# arduinoboard.net
KiCad netlist of a schematic drawn in EAGLE
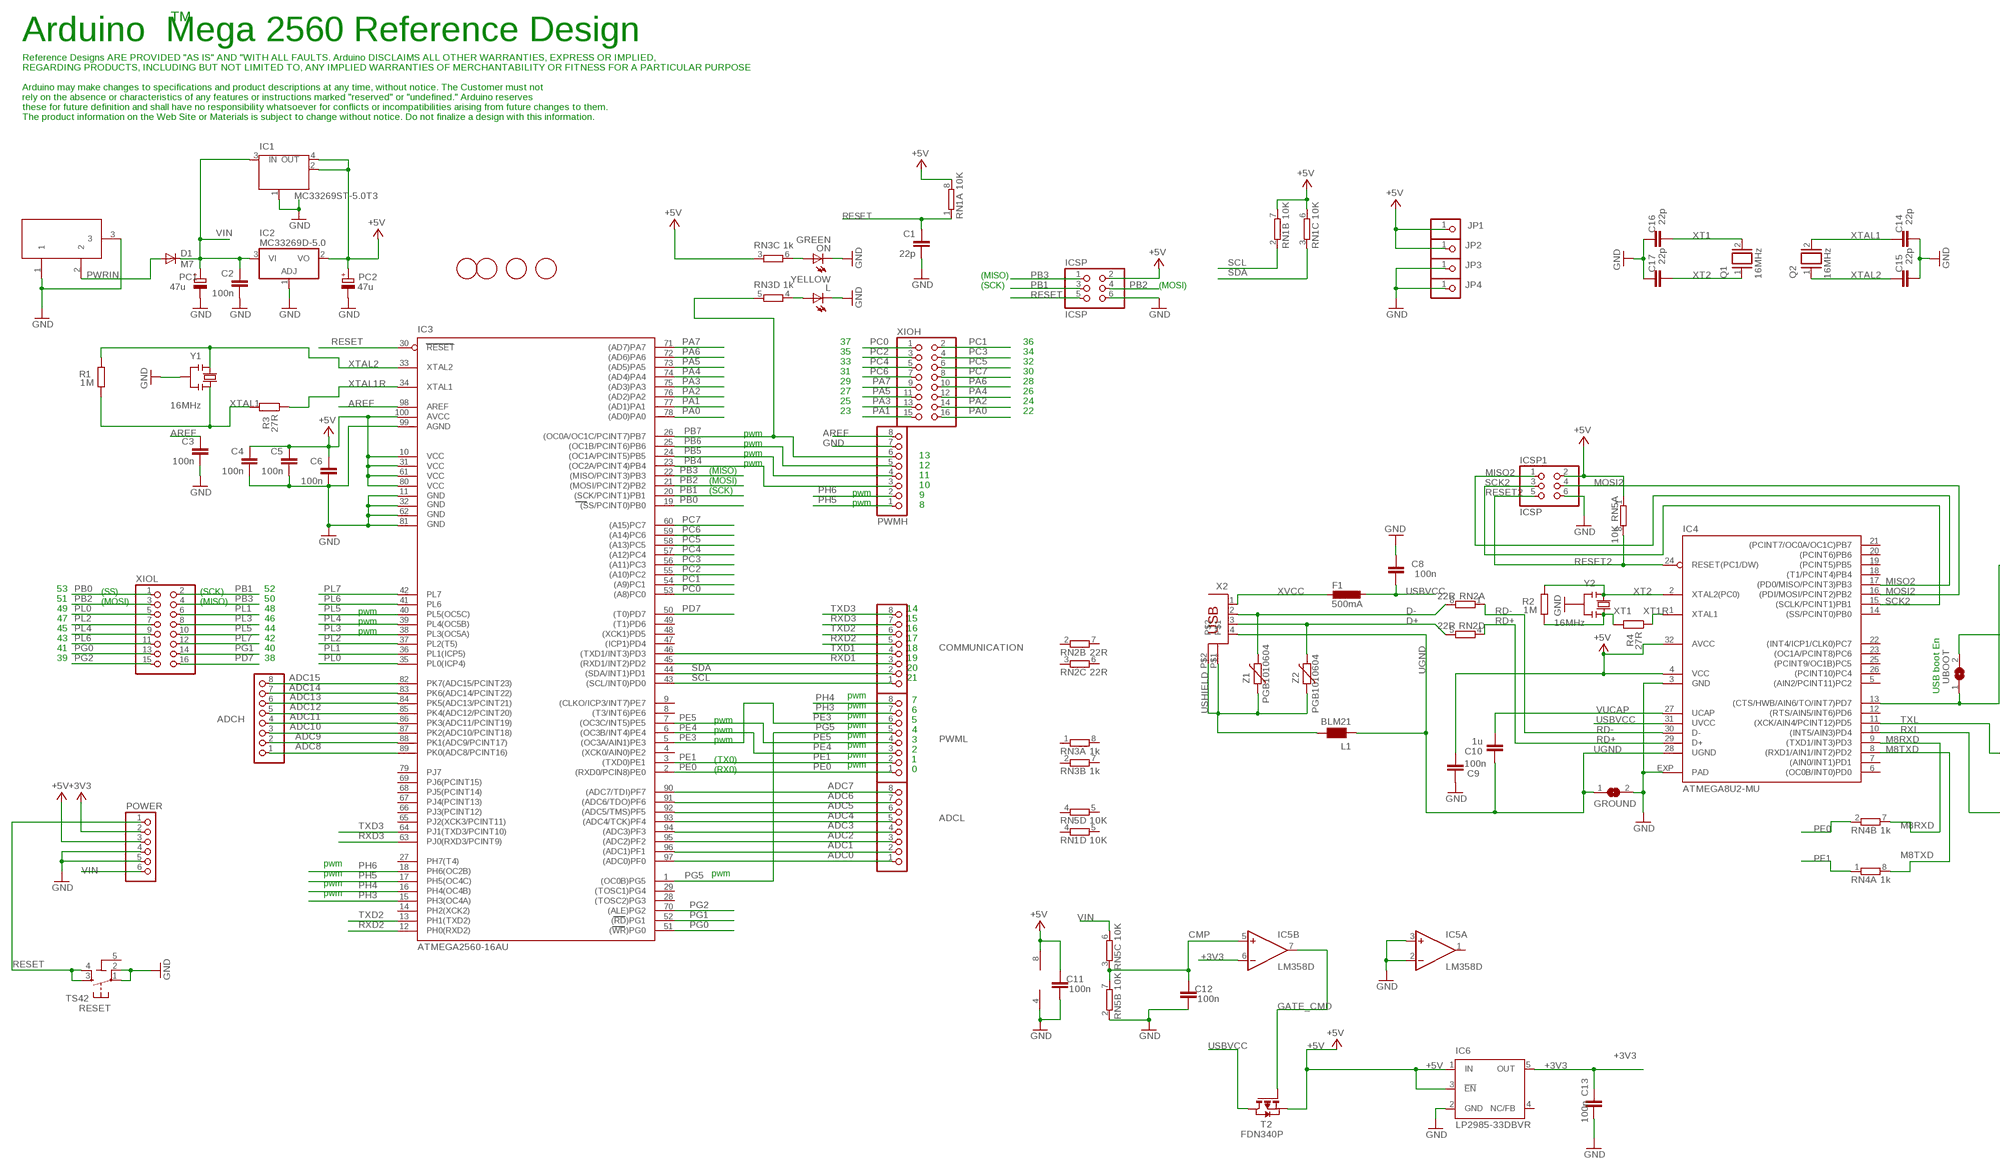
[diagram p0: schematic, sheet 1, part 1 of 2]
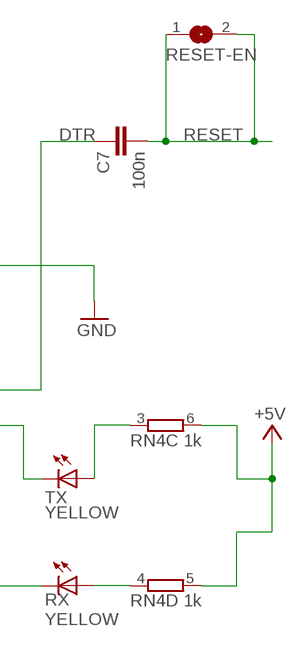
[diagram p1: schematic, sheet 1, part 2 of 2]

(export (version "E")
  (design (tool "Eeschema 10.0.6"))
  (components
    (comp (ref "ADCH")
      (value "PINHD-1X8")
      (footprint "eagle-import:1X08")
      (libsource (lib "eagle-import") (part "PINHD-1X8"))
    )
    (comp (ref "ADCL")
      (value "PINHD-1X8")
      (footprint "eagle-import:1X08")
      (libsource (lib "eagle-import") (part "PINHD-1X8"))
    )
    (comp (ref "C1")
      (value "22p")
      (footprint "eagle-import:C0603-ROUND")
      (libsource (lib "eagle-import") (part "C-EU0603-RND"))
    )
    (comp (ref "C2")
      (value "100n")
      (footprint "eagle-import:C0603-ROUND")
      (libsource (lib "eagle-import") (part "C-EU0603-RND"))
    )
    (comp (ref "C3")
      (value "100n")
      (footprint "eagle-import:C0603-ROUND")
      (libsource (lib "eagle-import") (part "C-EU0603-RND"))
    )
    (comp (ref "C4")
      (value "100n")
      (footprint "eagle-import:C0603-ROUND")
      (libsource (lib "eagle-import") (part "C-EU0603-RND"))
    )
    (comp (ref "C5")
      (value "100n")
      (footprint "eagle-import:C0603-ROUND")
      (libsource (lib "eagle-import") (part "C-EU0603-RND"))
    )
    (comp (ref "C6")
      (value "100n")
      (footprint "eagle-import:C0603-ROUND")
      (libsource (lib "eagle-import") (part "C-EU0603-RND"))
    )
    (comp (ref "C7")
      (value "100n")
      (footprint "eagle-import:C0603-ROUND")
      (libsource (lib "eagle-import") (part "C-EU0603-RND"))
    )
    (comp (ref "C8")
      (value "100n")
      (footprint "eagle-import:C0603")
      (libsource (lib "eagle-import") (part "rcl_C-EUC0603"))
    )
    (comp (ref "C9")
      (value "100n")
      (footprint "eagle-import:C0603-ROUND")
      (libsource (lib "eagle-import") (part "C-EU0603-RND"))
    )
    (comp (ref "C10")
      (value "1u")
      (footprint "eagle-import:C0603-ROUND")
      (libsource (lib "eagle-import") (part "C-EU0603-RND"))
    )
    (comp (ref "C11")
      (value "100n")
      (footprint "eagle-import:C0603")
      (libsource (lib "eagle-import") (part "rcl_C-EUC0603"))
    )
    (comp (ref "C12")
      (value "100n")
      (footprint "eagle-import:C0603-ROUND")
      (libsource (lib "eagle-import") (part "C-EU0603-RND"))
    )
    (comp (ref "C13")
      (value "100n")
      (footprint "eagle-import:C0603-ROUND")
      (libsource (lib "eagle-import") (part "C-EU0603-RND"))
    )
    (comp (ref "C14")
      (value "22p")
      (footprint "eagle-import:C0603-ROUND")
      (libsource (lib "eagle-import") (part "C-EU0603-RND"))
    )
    (comp (ref "C15")
      (value "22p")
      (footprint "eagle-import:C0603-ROUND")
      (libsource (lib "eagle-import") (part "C-EU0603-RND"))
    )
    (comp (ref "C16")
      (value "22p")
      (footprint "eagle-import:C0603-ROUND")
      (libsource (lib "eagle-import") (part "C-EU0603-RND"))
    )
    (comp (ref "C17")
      (value "22p")
      (footprint "eagle-import:C0603-ROUND")
      (libsource (lib "eagle-import") (part "C-EU0603-RND"))
    )
    (comp (ref "COMMUNICATION")
      (value "PINHD-1X8")
      (footprint "eagle-import:1X08")
      (libsource (lib "eagle-import") (part "PINHD-1X8"))
    )
    (comp (ref "D1")
      (value "M7")
      (footprint "eagle-import:SMB")
      (libsource (lib "eagle-import") (part "DIODE-SMB"))
    )
    (comp (ref "F1")
      (value "500mA")
      (footprint "eagle-import:L1812")
      (libsource (lib "eagle-import") (part "L-EUL1812"))
    )
    (comp (ref "GROUND")
      (value "SJ")
      (footprint "eagle-import:SJ")
      (libsource (lib "eagle-import") (part "SJ"))
    )
    (comp (ref "IC1")
      (value "MC33269ST-5.0T3")
      (footprint "eagle-import:SOT223")
      (libsource (lib "eagle-import") (part "MC33269ST-3.3T3"))
    )
    (comp (ref "IC2")
      (value "MC33269D-5.0")
      (footprint "eagle-import:DPACK")
      (libsource (lib "eagle-import") (part "MC33269?D-5.0"))
    )
    (comp (ref "IC3")
      (value "ATMEGA2560-16AU")
      (footprint "eagle-import:TQFP100")
      (libsource (lib "eagle-import") (part "ATMEGAAU1280-16"))
    )
    (comp (ref "IC4")
      (value "ATMEGA8U2-MU")
      (footprint "eagle-import:QFN32")
      (libsource (lib "eagle-import") (part "ATMEGA8U2-MU"))
    )
    (comp (ref "IC5")
      (value "LM358D")
      (footprint "eagle-import:SO08")
      (libsource (lib "eagle-import") (part "LM358D"))
    )
    (comp (ref "IC6")
      (value "LP2985-33DBVR")
      (footprint "eagle-import:SOT23-DBV")
      (libsource (lib "eagle-import") (part "TPS77033"))
    )
    (comp (ref "ICSP")
      (value "ICSP")
      (footprint "eagle-import:2X03")
      (libsource (lib "eagle-import") (part "PINHD-2X3"))
    )
    (comp (ref "ICSP1")
      (value "ICSP")
      (footprint "eagle-import:2X03")
      (libsource (lib "eagle-import") (part "PINHD-2X3"))
    )
    (comp (ref "JP1")
      (value "PINHD-1X1")
      (footprint "eagle-import:1X01")
      (libsource (lib "eagle-import") (part "PINHD-1X1"))
    )
    (comp (ref "JP2")
      (value "PINHD-1X1")
      (footprint "eagle-import:1X01")
      (libsource (lib "eagle-import") (part "PINHD-1X1"))
    )
    (comp (ref "JP3")
      (value "PINHD-1X1")
      (footprint "eagle-import:1X01")
      (libsource (lib "eagle-import") (part "PINHD-1X1"))
    )
    (comp (ref "JP4")
      (value "PINHD-1X1")
      (footprint "eagle-import:1X01")
      (libsource (lib "eagle-import") (part "PINHD-1X1"))
    )
    (comp (ref "L")
      (value "YELLOW")
      (footprint "eagle-import:CHIP-LED0805")
      (libsource (lib "eagle-import") (part "LEDCHIP-LED0805"))
    )
    (comp (ref "L1")
      (value "BLM21")
      (footprint "eagle-import:0805")
      (libsource (lib "eagle-import") (part "WE-CBF_0805"))
    )
    (comp (ref "ON")
      (value "GREEN")
      (footprint "eagle-import:CHIP-LED0805")
      (libsource (lib "eagle-import") (part "LEDCHIP-LED0805"))
    )
    (comp (ref "PC1")
      (value "47u")
      (footprint "eagle-import:PANASONIC_D")
      (libsource (lib "eagle-import") (part "CPOL-EUD"))
    )
    (comp (ref "PC2")
      (value "47u")
      (footprint "eagle-import:PANASONIC_D")
      (libsource (lib "eagle-import") (part "CPOL-EUD"))
    )
    (comp (ref "POWER")
      (value "PINHD-1X6")
      (footprint "eagle-import:1X06")
      (libsource (lib "eagle-import") (part "PINHD-1X6"))
    )
    (comp (ref "PWMH")
      (value "PINHD-1X8")
      (footprint "eagle-import:1X08")
      (libsource (lib "eagle-import") (part "PINHD-1X8"))
    )
    (comp (ref "PWML")
      (value "PINHD-1X8")
      (footprint "eagle-import:1X08")
      (libsource (lib "eagle-import") (part "PINHD-1X8"))
    )
    (comp (ref "Q1")
      (value "16MHz")
      (footprint "eagle-import:QS")
      (libsource (lib "eagle-import") (part "XTAL/S"))
    )
    (comp (ref "Q2")
      (value "16MHz")
      (footprint "eagle-import:QS")
      (libsource (lib "eagle-import") (part "XTAL/S"))
    )
    (comp (ref "R1")
      (value "1M")
      (footprint "eagle-import:R0603-ROUND")
      (libsource (lib "eagle-import") (part "R-EU_R0603"))
    )
    (comp (ref "R2")
      (value "1M")
      (footprint "eagle-import:R0603-ROUND")
      (libsource (lib "eagle-import") (part "R-EU_R0603"))
    )
    (comp (ref "R3")
      (value "27R")
      (footprint "eagle-import:R0603-ROUND")
      (libsource (lib "eagle-import") (part "R-EU_R0603"))
    )
    (comp (ref "R4")
      (value "27R")
      (footprint "eagle-import:R0603-ROUND")
      (libsource (lib "eagle-import") (part "R-EU_R0603"))
    )
    (comp (ref "RESET")
      (value "TS42")
      (footprint "eagle-import:TS42")
      (libsource (lib "eagle-import") (part "TS42"))
    )
    (comp (ref "RESET-EN")
      (value "SJ")
      (footprint "eagle-import:SJ")
      (libsource (lib "eagle-import") (part "SJ"))
    )
    (comp (ref "RN1")
      (value "10K")
      (footprint "eagle-import:CAT16")
      (libsource (lib "eagle-import") (part "4R-NCAT16"))
    )
    (comp (ref "RN2")
      (value "22R")
      (footprint "eagle-import:CAY16")
      (libsource (lib "eagle-import") (part "4R-NCAY16"))
    )
    (comp (ref "RN3")
      (value "1k")
      (footprint "eagle-import:CAY16")
      (libsource (lib "eagle-import") (part "4R-NCAY16"))
    )
    (comp (ref "RN4")
      (value "1k")
      (footprint "eagle-import:CAY16")
      (libsource (lib "eagle-import") (part "4R-NCAY16"))
    )
    (comp (ref "RN5")
      (value "10K")
      (footprint "eagle-import:CAT16")
      (libsource (lib "eagle-import") (part "4R-NCAT16"))
    )
    (comp (ref "RX")
      (value "YELLOW")
      (footprint "eagle-import:CHIP-LED0805")
      (libsource (lib "eagle-import") (part "LEDCHIP-LED0805"))
    )
    (comp (ref "T2")
      (value "FDN340P")
      (footprint "eagle-import:SOT-23")
      (libsource (lib "eagle-import") (part "PMOSSOT23"))
    )
    (comp (ref "TX")
      (value "YELLOW")
      (footprint "eagle-import:CHIP-LED0805")
      (libsource (lib "eagle-import") (part "LEDCHIP-LED0805"))
    )
    (comp (ref "U$2")
      (value "FIDUCIALMOUNT")
      (footprint "eagle-import:FIDUCIA-MOUNT")
      (libsource (lib "eagle-import") (part "FIDUCIALMOUNT"))
    )
    (comp (ref "U$3")
      (value "FIDUCIALMOUNT")
      (footprint "eagle-import:FIDUCIA-MOUNT")
      (libsource (lib "eagle-import") (part "FIDUCIALMOUNT"))
    )
    (comp (ref "U$4")
      (value "FIDUCIALMOUNT")
      (footprint "eagle-import:FIDUCIA-MOUNT")
      (libsource (lib "eagle-import") (part "FIDUCIALMOUNT"))
    )
    (comp (ref "U$5")
      (value "FIDUCIALMOUNT")
      (footprint "eagle-import:FIDUCIA-MOUNT")
      (libsource (lib "eagle-import") (part "FIDUCIALMOUNT"))
    )
    (comp (ref "UBOOT")
      (value "SJ")
      (footprint "eagle-import:SJ")
      (libsource (lib "eagle-import") (part "SJ"))
    )
    (comp (ref "X1")
      (value "DC21MMX")
      (footprint "eagle-import:DC-21MM")
      (libsource (lib "eagle-import") (part "DC21MMX"))
    )
    (comp (ref "X2")
      (value "PN61729")
      (footprint "eagle-import:PN61729")
      (libsource (lib "eagle-import") (part "PN61729"))
    )
    (comp (ref "XIOH")
      (value "PINHD-2X8")
      (footprint "eagle-import:2X08")
      (libsource (lib "eagle-import") (part "PINHD-2X8"))
    )
    (comp (ref "XIOL")
      (value "PINHD-2X8")
      (footprint "eagle-import:2X08")
      (libsource (lib "eagle-import") (part "PINHD-2X8"))
    )
    (comp (ref "Y1")
      (value "16MHz")
      (footprint "eagle-import:RESONATOR")
      (libsource (lib "eagle-import") (part "RESONATORMU"))
    )
    (comp (ref "Y2")
      (value "16MHz")
      (footprint "eagle-import:RESONATOR")
      (libsource (lib "eagle-import") (part "RESONATORMU"))
    )
    (comp (ref "Z1")
      (value "PGB1010604")
      (footprint "eagle-import:CT_CN0603")
      (libsource (lib "eagle-import") (part "VARISTORCN0603"))
    )
    (comp (ref "Z2")
      (value "PGB1010604")
      (footprint "eagle-import:CT_CN0603")
      (libsource (lib "eagle-import") (part "VARISTORCN0603"))
    )
  )
  (nets
    (net (code "1") (name "+3V3") (class "Default")
      (node (ref "C13") (pin "2") (pinfunction "2_2") (pintype "passive"))
      (node (ref "IC5") (pin "6") (pinfunction "-IN_6") (pintype "input"))
      (node (ref "IC6") (pin "5") (pinfunction "OUT_5") (pintype "passive"))
      (node (ref "POWER") (pin "2") (pinfunction "2_2") (pintype "passive"))
    )
    (net (code "2") (name "+5V") (class "Default")
      (node (ref "C11") (pin "2") (pinfunction "2_2") (pintype "passive"))
      (node (ref "C4") (pin "1") (pinfunction "1_1") (pintype "passive"))
      (node (ref "C5") (pin "1") (pinfunction "1_1") (pintype "passive"))
      (node (ref "C6") (pin "1") (pinfunction "1_1") (pintype "passive"))
      (node (ref "C9") (pin "1") (pinfunction "1_1") (pintype "passive"))
      (node (ref "IC1") (pin "2") (pinfunction "OUT_2") (pintype "passive"))
      (node (ref "IC1") (pin "4") (pinfunction "OUT_4") (pintype "passive"))
      (node (ref "IC2") (pin "2") (pinfunction "VO_2") (pintype "passive"))
      (node (ref "IC3") (pin "10") (pinfunction "VCC_10") (pintype "power_in"))
      (node (ref "IC3") (pin "100") (pinfunction "AVCC_100") (pintype "power_in"))
      (node (ref "IC3") (pin "31") (pinfunction "VCC1_31") (pintype "power_in"))
      (node (ref "IC3") (pin "61") (pinfunction "VCC2_61") (pintype "power_in"))
      (node (ref "IC3") (pin "80") (pinfunction "VCC3_80") (pintype "power_in"))
      (node (ref "IC4") (pin "32") (pinfunction "AVCC_32") (pintype "power_in"))
      (node (ref "IC4") (pin "4") (pinfunction "VCC_4") (pintype "power_in"))
      (node (ref "IC5") (pin "8") (pinfunction "V+_8") (pintype "power_in"))
      (node (ref "IC6") (pin "1") (pinfunction "IN_1") (pintype "input"))
      (node (ref "IC6") (pin "3") (pinfunction "~{EN}_3") (pintype "input"))
      (node (ref "ICSP") (pin "2") (pinfunction "2_2") (pintype "passive"))
      (node (ref "ICSP1") (pin "2") (pinfunction "2_2") (pintype "passive"))
      (node (ref "JP1") (pin "1") (pinfunction "1_1") (pintype "passive"))
      (node (ref "JP2") (pin "1") (pinfunction "1_1") (pintype "passive"))
      (node (ref "PC2") (pin "+") (pinfunction "+_+") (pintype "passive"))
      (node (ref "POWER") (pin "3") (pinfunction "3_3") (pintype "passive"))
      (node (ref "RN1") (pin "6") (pinfunction "2_6") (pintype "passive"))
      (node (ref "RN1") (pin "7") (pinfunction "2_7") (pintype "passive"))
      (node (ref "RN1") (pin "8") (pinfunction "2_8") (pintype "passive"))
      (node (ref "RN3") (pin "3") (pinfunction "1_3") (pintype "passive"))
      (node (ref "RN4") (pin "5") (pinfunction "2_5") (pintype "passive"))
      (node (ref "RN4") (pin "6") (pinfunction "2_6") (pintype "passive"))
      (node (ref "RN5") (pin "1") (pinfunction "1_1") (pintype "passive"))
      (node (ref "T2") (pin "2") (pinfunction "S_2") (pintype "passive"))
    )
    (net (code "3") (name "/5-GND") (class "Default")
      (node (ref "RESET") (pin "5") (pinfunction "5-GND_5") (pintype "power_in"))
    )
    (net (code "4") (name "/ADC0") (class "Default")
      (node (ref "ADCL") (pin "1") (pinfunction "1_1") (pintype "passive"))
      (node (ref "IC3") (pin "97") (pinfunction "(ADC0)PF0_97") (pintype "bidirectional"))
    )
    (net (code "5") (name "/ADC1") (class "Default")
      (node (ref "ADCL") (pin "2") (pinfunction "2_2") (pintype "passive"))
      (node (ref "IC3") (pin "96") (pinfunction "(ADC1)PF1_96") (pintype "bidirectional"))
    )
    (net (code "6") (name "/ADC2") (class "Default")
      (node (ref "ADCL") (pin "3") (pinfunction "3_3") (pintype "passive"))
      (node (ref "IC3") (pin "95") (pinfunction "(ADC2)PF2_95") (pintype "bidirectional"))
    )
    (net (code "7") (name "/ADC3") (class "Default")
      (node (ref "ADCL") (pin "4") (pinfunction "4_4") (pintype "passive"))
      (node (ref "IC3") (pin "94") (pinfunction "(ADC3)PF3_94") (pintype "bidirectional"))
    )
    (net (code "8") (name "/ADC4") (class "Default")
      (node (ref "ADCL") (pin "5") (pinfunction "5_5") (pintype "passive"))
      (node (ref "IC3") (pin "93") (pinfunction "(ADC4/TCK)PF4_93") (pintype "bidirectional"))
    )
    (net (code "9") (name "/ADC5") (class "Default")
      (node (ref "ADCL") (pin "6") (pinfunction "6_6") (pintype "passive"))
      (node (ref "IC3") (pin "92") (pinfunction "(ADC5/TMS)PF5_92") (pintype "bidirectional"))
    )
    (net (code "10") (name "/ADC6") (class "Default")
      (node (ref "ADCL") (pin "7") (pinfunction "7_7") (pintype "passive"))
      (node (ref "IC3") (pin "91") (pinfunction "(ADC6/TDO)PF6_91") (pintype "bidirectional"))
    )
    (net (code "11") (name "/ADC7") (class "Default")
      (node (ref "ADCL") (pin "8") (pinfunction "8_8") (pintype "passive"))
      (node (ref "IC3") (pin "90") (pinfunction "(ADC7/TDI)PF7_90") (pintype "bidirectional"))
    )
    (net (code "12") (name "/ADC8") (class "Default")
      (node (ref "ADCH") (pin "1") (pinfunction "1_1") (pintype "passive"))
      (node (ref "IC3") (pin "89") (pinfunction "PK0(ADC8/PCINT16)_89") (pintype "bidirectional"))
    )
    (net (code "13") (name "/ADC9") (class "Default")
      (node (ref "ADCH") (pin "2") (pinfunction "2_2") (pintype "passive"))
      (node (ref "IC3") (pin "88") (pinfunction "PK1(ADC9/PCINT17)_88") (pintype "bidirectional"))
    )
    (net (code "14") (name "/ADC10") (class "Default")
      (node (ref "ADCH") (pin "3") (pinfunction "3_3") (pintype "passive"))
      (node (ref "IC3") (pin "87") (pinfunction "PK2(ADC10/PCINT18)_87") (pintype "bidirectional"))
    )
    (net (code "15") (name "/ADC11") (class "Default")
      (node (ref "ADCH") (pin "4") (pinfunction "4_4") (pintype "passive"))
      (node (ref "IC3") (pin "86") (pinfunction "PK3(ADC11/PCINT19)_86") (pintype "bidirectional"))
    )
    (net (code "16") (name "/ADC12") (class "Default")
      (node (ref "ADCH") (pin "5") (pinfunction "5_5") (pintype "passive"))
      (node (ref "IC3") (pin "85") (pinfunction "PK4(ADC12/PCINT20)_85") (pintype "bidirectional"))
    )
    (net (code "17") (name "/ADC13") (class "Default")
      (node (ref "ADCH") (pin "6") (pinfunction "6_6") (pintype "passive"))
      (node (ref "IC3") (pin "84") (pinfunction "PK5(ADC13/PCINT21)_84") (pintype "bidirectional"))
    )
    (net (code "18") (name "/ADC14") (class "Default")
      (node (ref "ADCH") (pin "7") (pinfunction "7_7") (pintype "passive"))
      (node (ref "IC3") (pin "83") (pinfunction "PK6(ADC14/PCINT22)_83") (pintype "bidirectional"))
    )
    (net (code "19") (name "/ADC15") (class "Default")
      (node (ref "ADCH") (pin "8") (pinfunction "8_8") (pintype "passive"))
      (node (ref "IC3") (pin "82") (pinfunction "PK7(ADC15/PCINT23)_82") (pintype "bidirectional"))
    )
    (net (code "20") (name "/AREF") (class "Default")
      (node (ref "C3") (pin "1") (pinfunction "1_1") (pintype "passive"))
      (node (ref "IC3") (pin "98") (pinfunction "AREF_98") (pintype "bidirectional"))
      (node (ref "PWMH") (pin "8") (pinfunction "8_8") (pintype "passive"))
    )
    (net (code "21") (name "/CMP") (class "Default")
      (node (ref "C12") (pin "2") (pinfunction "2_2") (pintype "passive"))
      (node (ref "IC5") (pin "5") (pinfunction "+IN_5") (pintype "input"))
      (node (ref "RN5") (pin "3") (pinfunction "1_3") (pintype "passive"))
      (node (ref "RN5") (pin "7") (pinfunction "2_7") (pintype "passive"))
    )
    (net (code "22") (name "/D+") (class "Default")
      (node (ref "RN2") (pin "5") (pinfunction "2_5") (pintype "passive"))
      (node (ref "X2") (pin "3") (pinfunction "3_3") (pintype "bidirectional"))
      (node (ref "Z2") (pin "2") (pinfunction "2_2") (pintype "passive"))
    )
    (net (code "23") (name "/D-") (class "Default")
      (node (ref "RN2") (pin "8") (pinfunction "2_8") (pintype "passive"))
      (node (ref "X2") (pin "2") (pinfunction "2_2") (pintype "bidirectional"))
      (node (ref "Z1") (pin "2") (pinfunction "2_2") (pintype "passive"))
    )
    (net (code "24") (name "/DTR") (class "Default")
      (node (ref "C7") (pin "1") (pinfunction "1_1") (pintype "passive"))
      (node (ref "IC4") (pin "13") (pinfunction "(CTS/HWB/AIN6/TO/INT7)PD7_13") (pintype "bidirectional"))
      (node (ref "UBOOT") (pin "1") (pinfunction "1_1") (pintype "passive"))
    )
    (net (code "25") (name "/GATE_CMD") (class "Default")
      (node (ref "IC5") (pin "7") (pinfunction "OUT_7") (pintype "output"))
      (node (ref "T2") (pin "3") (pinfunction "G_3") (pintype "passive"))
    )
    (net (code "26") (name "/M8RXD") (class "Default")
      (node (ref "IC4") (pin "9") (pinfunction "(TXD1/INT3)PD3_9") (pintype "bidirectional"))
      (node (ref "RN4") (pin "7") (pinfunction "2_7") (pintype "passive"))
    )
    (net (code "27") (name "/M8TXD") (class "Default")
      (node (ref "IC4") (pin "8") (pinfunction "(RXD1/AIN1/INT2)PD2_8") (pintype "bidirectional"))
      (node (ref "RN4") (pin "8") (pinfunction "2_8") (pintype "passive"))
    )
    (net (code "28") (name "/MISO2") (class "Default")
      (node (ref "IC4") (pin "17") (pinfunction "(PD0/MISO/PCINT3)PB3_17") (pintype "bidirectional"))
      (node (ref "ICSP1") (pin "1") (pinfunction "1_1") (pintype "passive"))
    )
    (net (code "29") (name "/MOSI2") (class "Default")
      (node (ref "IC4") (pin "16") (pinfunction "(PDI/MOSI/PCINT2)PB2_16") (pintype "bidirectional"))
      (node (ref "ICSP1") (pin "4") (pinfunction "4_4") (pintype "passive"))
    )
    (net (code "30") (name "/PA0") (class "Default")
      (node (ref "IC3") (pin "78") (pinfunction "(AD0)PA0_78") (pintype "bidirectional"))
      (node (ref "XIOH") (pin "16") (pinfunction "16_16") (pintype "passive"))
    )
    (net (code "31") (name "/PA1") (class "Default")
      (node (ref "IC3") (pin "77") (pinfunction "(AD1)PA1_77") (pintype "bidirectional"))
      (node (ref "XIOH") (pin "15") (pinfunction "15_15") (pintype "passive"))
    )
    (net (code "32") (name "/PA2") (class "Default")
      (node (ref "IC3") (pin "76") (pinfunction "(AD2)PA2_76") (pintype "bidirectional"))
      (node (ref "XIOH") (pin "14") (pinfunction "14_14") (pintype "passive"))
    )
    (net (code "33") (name "/PA3") (class "Default")
      (node (ref "IC3") (pin "75") (pinfunction "(AD3)PA3_75") (pintype "bidirectional"))
      (node (ref "XIOH") (pin "13") (pinfunction "13_13") (pintype "passive"))
    )
    (net (code "34") (name "/PA4") (class "Default")
      (node (ref "IC3") (pin "74") (pinfunction "(AD4)PA4_74") (pintype "bidirectional"))
      (node (ref "XIOH") (pin "12") (pinfunction "12_12") (pintype "passive"))
    )
    (net (code "35") (name "/PA5") (class "Default")
      (node (ref "IC3") (pin "73") (pinfunction "(AD5)PA5_73") (pintype "bidirectional"))
      (node (ref "XIOH") (pin "11") (pinfunction "11_11") (pintype "passive"))
    )
    (net (code "36") (name "/PA6") (class "Default")
      (node (ref "IC3") (pin "72") (pinfunction "(AD6)PA6_72") (pintype "bidirectional"))
      (node (ref "XIOH") (pin "10") (pinfunction "10_10") (pintype "passive"))
    )
    (net (code "37") (name "/PA7") (class "Default")
      (node (ref "IC3") (pin "71") (pinfunction "(AD7)PA7_71") (pintype "bidirectional"))
      (node (ref "XIOH") (pin "9") (pinfunction "9_9") (pintype "passive"))
    )
    (net (code "38") (name "/PB0") (class "Default")
      (node (ref "IC3") (pin "19") (pinfunction "(SS/PCINT0)PB0_19") (pintype "bidirectional"))
      (node (ref "XIOL") (pin "1") (pinfunction "1_1") (pintype "passive"))
    )
    (net (code "39") (name "/PB1") (class "Default")
      (node (ref "IC3") (pin "20") (pinfunction "(SCK/PCINT1)PB1_20") (pintype "bidirectional"))
      (node (ref "ICSP") (pin "3") (pinfunction "3_3") (pintype "passive"))
      (node (ref "XIOL") (pin "2") (pinfunction "2_2") (pintype "passive"))
    )
    (net (code "40") (name "/PB2") (class "Default")
      (node (ref "IC3") (pin "21") (pinfunction "(MOSI/PCINT2)PB2_21") (pintype "bidirectional"))
      (node (ref "ICSP") (pin "4") (pinfunction "4_4") (pintype "passive"))
      (node (ref "XIOL") (pin "3") (pinfunction "3_3") (pintype "passive"))
    )
    (net (code "41") (name "/PB3") (class "Default")
      (node (ref "IC3") (pin "22") (pinfunction "(MISO/PCINT3)PB3_22") (pintype "bidirectional"))
      (node (ref "ICSP") (pin "1") (pinfunction "1_1") (pintype "passive"))
      (node (ref "XIOL") (pin "4") (pinfunction "4_4") (pintype "passive"))
    )
    (net (code "42") (name "/PB4") (class "Default")
      (node (ref "IC3") (pin "23") (pinfunction "(OC2A/PCINT4)PB4_23") (pintype "bidirectional"))
      (node (ref "PWMH") (pin "3") (pinfunction "3_3") (pintype "passive"))
    )
    (net (code "43") (name "/PB5") (class "Default")
      (node (ref "IC3") (pin "24") (pinfunction "(OC1A/PCINT5)PB5_24") (pintype "bidirectional"))
      (node (ref "PWMH") (pin "4") (pinfunction "4_4") (pintype "passive"))
    )
    (net (code "44") (name "/PB6") (class "Default")
      (node (ref "IC3") (pin "25") (pinfunction "(OC1B/PCINT6)PB6_25") (pintype "bidirectional"))
      (node (ref "PWMH") (pin "5") (pinfunction "5_5") (pintype "passive"))
    )
    (net (code "45") (name "/PB7") (class "Default")
      (node (ref "IC3") (pin "26") (pinfunction "(OC0A/OC1C/PCINT7)PB7_26") (pintype "bidirectional"))
      (node (ref "PWMH") (pin "6") (pinfunction "6_6") (pintype "passive"))
      (node (ref "RN3") (pin "5") (pinfunction "2_5") (pintype "passive"))
    )
    (net (code "46") (name "/PC0") (class "Default")
      (node (ref "IC3") (pin "53") (pinfunction "(A8)PC0_53") (pintype "bidirectional"))
      (node (ref "XIOH") (pin "1") (pinfunction "1_1") (pintype "passive"))
    )
    (net (code "47") (name "/PC1") (class "Default")
      (node (ref "IC3") (pin "54") (pinfunction "(A9)PC1_54") (pintype "bidirectional"))
      (node (ref "XIOH") (pin "2") (pinfunction "2_2") (pintype "passive"))
    )
    (net (code "48") (name "/PC2") (class "Default")
      (node (ref "IC3") (pin "55") (pinfunction "(A10)PC2_55") (pintype "bidirectional"))
      (node (ref "XIOH") (pin "3") (pinfunction "3_3") (pintype "passive"))
    )
    (net (code "49") (name "/PC3") (class "Default")
      (node (ref "IC3") (pin "56") (pinfunction "(A11)PC3_56") (pintype "bidirectional"))
      (node (ref "XIOH") (pin "4") (pinfunction "4_4") (pintype "passive"))
    )
    (net (code "50") (name "/PC4") (class "Default")
      (node (ref "IC3") (pin "57") (pinfunction "(A12)PC4_57") (pintype "bidirectional"))
      (node (ref "XIOH") (pin "5") (pinfunction "5_5") (pintype "passive"))
    )
    (net (code "51") (name "/PC5") (class "Default")
      (node (ref "IC3") (pin "58") (pinfunction "(A13)PC5_58") (pintype "bidirectional"))
      (node (ref "XIOH") (pin "6") (pinfunction "6_6") (pintype "passive"))
    )
    (net (code "52") (name "/PC6") (class "Default")
      (node (ref "IC3") (pin "59") (pinfunction "(A14)PC6_59") (pintype "bidirectional"))
      (node (ref "XIOH") (pin "7") (pinfunction "7_7") (pintype "passive"))
    )
    (net (code "53") (name "/PC7") (class "Default")
      (node (ref "IC3") (pin "60") (pinfunction "(A15)PC7_60") (pintype "bidirectional"))
      (node (ref "XIOH") (pin "8") (pinfunction "8_8") (pintype "passive"))
    )
    (net (code "54") (name "/PD7") (class "Default")
      (node (ref "IC3") (pin "50") (pinfunction "(T0)PD7_50") (pintype "bidirectional"))
      (node (ref "XIOL") (pin "16") (pinfunction "16_16") (pintype "passive"))
    )
    (net (code "55") (name "/PE0") (class "Default")
      (node (ref "IC3") (pin "2") (pinfunction "(RXD0/PCIN8)PE0_2") (pintype "bidirectional"))
      (node (ref "PWML") (pin "1") (pinfunction "1_1") (pintype "passive"))
      (node (ref "RN4") (pin "2") (pinfunction "1_2") (pintype "passive"))
    )
    (net (code "56") (name "/PE1") (class "Default")
      (node (ref "IC3") (pin "3") (pinfunction "(TXD0)PE1_3") (pintype "bidirectional"))
      (node (ref "PWML") (pin "2") (pinfunction "2_2") (pintype "passive"))
      (node (ref "RN4") (pin "1") (pinfunction "1_1") (pintype "passive"))
    )
    (net (code "57") (name "/PE3") (class "Default")
      (node (ref "IC3") (pin "5") (pinfunction "(OC3A/AIN1)PE3_5") (pintype "bidirectional"))
      (node (ref "PWML") (pin "6") (pinfunction "6_6") (pintype "passive"))
    )
    (net (code "58") (name "/PE4") (class "Default")
      (node (ref "IC3") (pin "6") (pinfunction "(OC3B/INT4)PE4_6") (pintype "bidirectional"))
      (node (ref "PWML") (pin "3") (pinfunction "3_3") (pintype "passive"))
    )
    (net (code "59") (name "/PE5") (class "Default")
      (node (ref "IC3") (pin "7") (pinfunction "(OC3C/INT5)PE5_7") (pintype "bidirectional"))
      (node (ref "PWML") (pin "4") (pinfunction "4_4") (pintype "passive"))
    )
    (net (code "60") (name "/PG0") (class "Default")
      (node (ref "IC3") (pin "51") (pinfunction "(WR)PG0_51") (pintype "bidirectional"))
      (node (ref "XIOL") (pin "13") (pinfunction "13_13") (pintype "passive"))
    )
    (net (code "61") (name "/PG1") (class "Default")
      (node (ref "IC3") (pin "52") (pinfunction "(RD)PG1_52") (pintype "bidirectional"))
      (node (ref "XIOL") (pin "14") (pinfunction "14_14") (pintype "passive"))
    )
    (net (code "62") (name "/PG2") (class "Default")
      (node (ref "IC3") (pin "70") (pinfunction "(ALE)PG2_70") (pintype "bidirectional"))
      (node (ref "XIOL") (pin "15") (pinfunction "15_15") (pintype "passive"))
    )
    (net (code "63") (name "/PG5") (class "Default")
      (node (ref "IC3") (pin "1") (pinfunction "(OC0B)PG5_1") (pintype "bidirectional"))
      (node (ref "PWML") (pin "5") (pinfunction "5_5") (pintype "passive"))
    )
    (net (code "64") (name "/PH3") (class "Default")
      (node (ref "IC3") (pin "15") (pinfunction "PH3(OC4A)_15") (pintype "bidirectional"))
      (node (ref "PWML") (pin "7") (pinfunction "7_7") (pintype "passive"))
    )
    (net (code "65") (name "/PH4") (class "Default")
      (node (ref "IC3") (pin "16") (pinfunction "PH4(OC4B)_16") (pintype "bidirectional"))
      (node (ref "PWML") (pin "8") (pinfunction "8_8") (pintype "passive"))
    )
    (net (code "66") (name "/PH5") (class "Default")
      (node (ref "IC3") (pin "17") (pinfunction "PH5(OC4C)_17") (pintype "bidirectional"))
      (node (ref "PWMH") (pin "1") (pinfunction "1_1") (pintype "passive"))
    )
    (net (code "67") (name "/PH6") (class "Default")
      (node (ref "IC3") (pin "18") (pinfunction "PH6(OC2B)_18") (pintype "bidirectional"))
      (node (ref "PWMH") (pin "2") (pinfunction "2_2") (pintype "passive"))
    )
    (net (code "68") (name "/PL0") (class "Default")
      (node (ref "IC3") (pin "35") (pinfunction "PL0(ICP4)_35") (pintype "bidirectional"))
      (node (ref "XIOL") (pin "5") (pinfunction "5_5") (pintype "passive"))
    )
    (net (code "69") (name "/PL1") (class "Default")
      (node (ref "IC3") (pin "36") (pinfunction "PL1(ICP5)_36") (pintype "bidirectional"))
      (node (ref "XIOL") (pin "6") (pinfunction "6_6") (pintype "passive"))
    )
    (net (code "70") (name "/PL2") (class "Default")
      (node (ref "IC3") (pin "37") (pinfunction "PL2(T5)_37") (pintype "bidirectional"))
      (node (ref "XIOL") (pin "7") (pinfunction "7_7") (pintype "passive"))
    )
    (net (code "71") (name "/PL3") (class "Default")
      (node (ref "IC3") (pin "38") (pinfunction "PL3(OC5A)_38") (pintype "bidirectional"))
      (node (ref "XIOL") (pin "8") (pinfunction "8_8") (pintype "passive"))
    )
    (net (code "72") (name "/PL4") (class "Default")
      (node (ref "IC3") (pin "39") (pinfunction "PL4(OC5B)_39") (pintype "bidirectional"))
      (node (ref "XIOL") (pin "9") (pinfunction "9_9") (pintype "passive"))
    )
    (net (code "73") (name "/PL5") (class "Default")
      (node (ref "IC3") (pin "40") (pinfunction "PL5(OC5C)_40") (pintype "bidirectional"))
      (node (ref "XIOL") (pin "10") (pinfunction "10_10") (pintype "passive"))
    )
    (net (code "74") (name "/PL6") (class "Default")
      (node (ref "IC3") (pin "41") (pinfunction "PL6_41") (pintype "bidirectional"))
      (node (ref "XIOL") (pin "11") (pinfunction "11_11") (pintype "passive"))
    )
    (net (code "75") (name "/PL7") (class "Default")
      (node (ref "IC3") (pin "42") (pinfunction "PL7_42") (pintype "bidirectional"))
      (node (ref "XIOL") (pin "12") (pinfunction "12_12") (pintype "passive"))
    )
    (net (code "76") (name "/PWRIN") (class "Default")
      (node (ref "D1") (pin "A") (pinfunction "A_A") (pintype "passive"))
      (node (ref "X1") (pin "2") (pinfunction "2_2") (pintype "power_in"))
    )
    (net (code "77") (name "/RD+") (class "Default")
      (node (ref "IC4") (pin "29") (pinfunction "D+_29") (pintype "bidirectional"))
      (node (ref "RN2") (pin "4") (pinfunction "1_4") (pintype "passive"))
    )
    (net (code "78") (name "/RD-") (class "Default")
      (node (ref "IC4") (pin "30") (pinfunction "D-_30") (pintype "bidirectional"))
      (node (ref "RN2") (pin "1") (pinfunction "1_1") (pintype "passive"))
    )
    (net (code "79") (name "/RESET") (class "Default")
      (node (ref "C1") (pin "1") (pinfunction "1_1") (pintype "passive"))
      (node (ref "C7") (pin "2") (pinfunction "2_2") (pintype "passive"))
      (node (ref "IC3") (pin "30") (pinfunction "RESET_30") (pintype "input"))
      (node (ref "ICSP") (pin "5") (pinfunction "5_5") (pintype "passive"))
      (node (ref "POWER") (pin "1") (pinfunction "1_1") (pintype "passive"))
      (node (ref "RESET") (pin "3") (pinfunction "3_3") (pintype "passive"))
      (node (ref "RESET") (pin "4") (pinfunction "4_4") (pintype "passive"))
      (node (ref "RESET-EN") (pin "1") (pinfunction "1_1") (pintype "passive"))
      (node (ref "RESET-EN") (pin "2") (pinfunction "2_2") (pintype "passive"))
      (node (ref "RN1") (pin "1") (pinfunction "1_1") (pintype "passive"))
    )
    (net (code "80") (name "/RESET2") (class "Default")
      (node (ref "IC4") (pin "24") (pinfunction "RESET(PC1/DW)_24") (pintype "input"))
      (node (ref "ICSP1") (pin "5") (pinfunction "5_5") (pintype "passive"))
      (node (ref "RN5") (pin "8") (pinfunction "2_8") (pintype "passive"))
    )
    (net (code "81") (name "/RXD1") (class "Default")
      (node (ref "COMMUNICATION") (pin "3") (pinfunction "3_3") (pintype "passive"))
      (node (ref "IC3") (pin "45") (pinfunction "(RXD1/INT2)PD2_45") (pintype "bidirectional"))
    )
    (net (code "82") (name "/RXD2") (class "Default")
      (node (ref "COMMUNICATION") (pin "5") (pinfunction "5_5") (pintype "passive"))
      (node (ref "IC3") (pin "12") (pinfunction "PH0(RXD2)_12") (pintype "bidirectional"))
    )
    (net (code "83") (name "/RXD3") (class "Default")
      (node (ref "COMMUNICATION") (pin "7") (pinfunction "7_7") (pintype "passive"))
      (node (ref "IC3") (pin "63") (pinfunction "PJ0(RXD3/PCINT9)_63") (pintype "bidirectional"))
    )
    (net (code "84") (name "/RXL") (class "Default")
      (node (ref "IC4") (pin "10") (pinfunction "(INT5/AIN3)PD4_10") (pintype "bidirectional"))
      (node (ref "RX") (pin "C") (pinfunction "C_C") (pintype "passive"))
    )
    (net (code "85") (name "/SCK2") (class "Default")
      (node (ref "IC4") (pin "15") (pinfunction "(SCLK/PCINT1)PB1_15") (pintype "bidirectional"))
      (node (ref "ICSP1") (pin "3") (pinfunction "3_3") (pintype "passive"))
    )
    (net (code "86") (name "/SCL") (class "Default")
      (node (ref "COMMUNICATION") (pin "1") (pinfunction "1_1") (pintype "passive"))
      (node (ref "IC3") (pin "43") (pinfunction "(SCL/INT0)PD0_43") (pintype "bidirectional"))
      (node (ref "RN1") (pin "2") (pinfunction "1_2") (pintype "passive"))
    )
    (net (code "87") (name "/SDA") (class "Default")
      (node (ref "COMMUNICATION") (pin "2") (pinfunction "2_2") (pintype "passive"))
      (node (ref "IC3") (pin "44") (pinfunction "(SDA/INT1)PD1_44") (pintype "bidirectional"))
      (node (ref "RN1") (pin "3") (pinfunction "1_3") (pintype "passive"))
    )
    (net (code "88") (name "/TXD1") (class "Default")
      (node (ref "COMMUNICATION") (pin "4") (pinfunction "4_4") (pintype "passive"))
      (node (ref "IC3") (pin "46") (pinfunction "(TXD1/INT3)PD3_46") (pintype "bidirectional"))
    )
    (net (code "89") (name "/TXD2") (class "Default")
      (node (ref "COMMUNICATION") (pin "6") (pinfunction "6_6") (pintype "passive"))
      (node (ref "IC3") (pin "13") (pinfunction "PH1(TXD2)_13") (pintype "bidirectional"))
    )
    (net (code "90") (name "/TXD3") (class "Default")
      (node (ref "COMMUNICATION") (pin "8") (pinfunction "8_8") (pintype "passive"))
      (node (ref "IC3") (pin "64") (pinfunction "PJ1(TXD3/PCINT10)_64") (pintype "bidirectional"))
    )
    (net (code "91") (name "/TXL") (class "Default")
      (node (ref "IC4") (pin "11") (pinfunction "(XCK/AIN4/PCINT12)PD5_11") (pintype "bidirectional"))
      (node (ref "TX") (pin "C") (pinfunction "C_C") (pintype "passive"))
    )
    (net (code "92") (name "/UGND") (class "Default")
      (node (ref "C10") (pin "2") (pinfunction "2_2") (pintype "passive"))
      (node (ref "GROUND") (pin "1") (pinfunction "1_1") (pintype "passive"))
      (node (ref "IC4") (pin "28") (pinfunction "UGND_28") (pintype "power_in"))
      (node (ref "L1") (pin "1") (pinfunction "1_1") (pintype "passive"))
      (node (ref "X2") (pin "4") (pinfunction "4_4") (pintype "bidirectional"))
    )
    (net (code "93") (name "/USBVCC") (class "Default")
      (node (ref "C8") (pin "1") (pinfunction "1_1") (pintype "passive"))
      (node (ref "F1") (pin "1") (pinfunction "1_1") (pintype "passive"))
      (node (ref "IC4") (pin "31") (pinfunction "UVCC_31") (pintype "power_in"))
      (node (ref "T2") (pin "1") (pinfunction "D_1") (pintype "passive"))
    )
    (net (code "94") (name "/USHIELD") (class "Default")
      (node (ref "L1") (pin "2") (pinfunction "2_2") (pintype "passive"))
      (node (ref "X2") (pin "P$1") (pinfunction "P$1_P$1") (pintype "bidirectional"))
      (node (ref "X2") (pin "P$2") (pinfunction "P$2_P$2") (pintype "bidirectional"))
      (node (ref "Z1") (pin "1") (pinfunction "1_1") (pintype "passive"))
      (node (ref "Z2") (pin "1") (pinfunction "1_1") (pintype "passive"))
    )
    (net (code "95") (name "/VIN") (class "Default")
      (node (ref "C2") (pin "1") (pinfunction "1_1") (pintype "passive"))
      (node (ref "D1") (pin "C") (pinfunction "C_C") (pintype "passive"))
      (node (ref "IC1") (pin "3") (pinfunction "IN_3") (pintype "input"))
      (node (ref "IC2") (pin "3") (pinfunction "VI_3") (pintype "input"))
      (node (ref "PC1") (pin "+") (pinfunction "+_+") (pintype "passive"))
      (node (ref "POWER") (pin "6") (pinfunction "6_6") (pintype "passive"))
      (node (ref "RN5") (pin "6") (pinfunction "2_6") (pintype "passive"))
    )
    (net (code "96") (name "/VUCAP") (class "Default")
      (node (ref "C10") (pin "1") (pinfunction "1_1") (pintype "passive"))
      (node (ref "IC4") (pin "27") (pinfunction "UCAP_27") (pintype "passive"))
    )
    (net (code "97") (name "/XT1") (class "Default")
      (node (ref "C16") (pin "1") (pinfunction "1_1") (pintype "passive"))
      (node (ref "Q1") (pin "2") (pinfunction "2_2") (pintype "passive"))
      (node (ref "R2") (pin "1") (pinfunction "1_1") (pintype "passive"))
      (node (ref "R4") (pin "2") (pinfunction "2_2") (pintype "passive"))
      (node (ref "Y2") (pin "3") (pinfunction "3_3") (pintype "passive"))
    )
    (net (code "98") (name "/XT1R") (class "Default")
      (node (ref "IC4") (pin "1") (pinfunction "XTAL1_1") (pintype "bidirectional"))
      (node (ref "R4") (pin "1") (pinfunction "1_1") (pintype "passive"))
    )
    (net (code "99") (name "/XT2") (class "Default")
      (node (ref "C17") (pin "1") (pinfunction "1_1") (pintype "passive"))
      (node (ref "IC4") (pin "2") (pinfunction "XTAL2(PC0)_2") (pintype "bidirectional"))
      (node (ref "Q1") (pin "1") (pinfunction "1_1") (pintype "passive"))
      (node (ref "R2") (pin "2") (pinfunction "2_2") (pintype "passive"))
      (node (ref "Y2") (pin "1") (pinfunction "1_1") (pintype "passive"))
    )
    (net (code "100") (name "/XTAL1") (class "Default")
      (node (ref "C14") (pin "2") (pinfunction "2_2") (pintype "passive"))
      (node (ref "Q2") (pin "2") (pinfunction "2_2") (pintype "passive"))
      (node (ref "R1") (pin "1") (pinfunction "1_1") (pintype "passive"))
      (node (ref "R3") (pin "2") (pinfunction "2_2") (pintype "passive"))
      (node (ref "Y1") (pin "3") (pinfunction "3_3") (pintype "passive"))
    )
    (net (code "101") (name "/XTAL1R") (class "Default")
      (node (ref "IC3") (pin "34") (pinfunction "XTAL1_34") (pintype "input"))
      (node (ref "R3") (pin "1") (pinfunction "1_1") (pintype "passive"))
    )
    (net (code "102") (name "/XTAL2") (class "Default")
      (node (ref "C15") (pin "2") (pinfunction "2_2") (pintype "passive"))
      (node (ref "IC3") (pin "33") (pinfunction "XTAL2_33") (pintype "output"))
      (node (ref "Q2") (pin "1") (pinfunction "1_1") (pintype "passive"))
      (node (ref "R1") (pin "2") (pinfunction "2_2") (pintype "passive"))
      (node (ref "Y1") (pin "1") (pinfunction "1_1") (pintype "passive"))
    )
    (net (code "103") (name "/XVCC") (class "Default")
      (node (ref "F1") (pin "2") (pinfunction "2_2") (pintype "passive"))
      (node (ref "X2") (pin "1") (pinfunction "1_1") (pintype "bidirectional"))
    )
    (net (code "104") (name "GND") (class "Default")
      (node (ref "C1") (pin "2") (pinfunction "2_2") (pintype "passive"))
      (node (ref "C11") (pin "1") (pinfunction "1_1") (pintype "passive"))
      (node (ref "C12") (pin "1") (pinfunction "1_1") (pintype "passive"))
      (node (ref "C13") (pin "1") (pinfunction "1_1") (pintype "passive"))
      (node (ref "C14") (pin "1") (pinfunction "1_1") (pintype "passive"))
      (node (ref "C15") (pin "1") (pinfunction "1_1") (pintype "passive"))
      (node (ref "C16") (pin "2") (pinfunction "2_2") (pintype "passive"))
      (node (ref "C17") (pin "2") (pinfunction "2_2") (pintype "passive"))
      (node (ref "C2") (pin "2") (pinfunction "2_2") (pintype "passive"))
      (node (ref "C3") (pin "2") (pinfunction "2_2") (pintype "passive"))
      (node (ref "C4") (pin "2") (pinfunction "2_2") (pintype "passive"))
      (node (ref "C5") (pin "2") (pinfunction "2_2") (pintype "passive"))
      (node (ref "C6") (pin "2") (pinfunction "2_2") (pintype "passive"))
      (node (ref "C8") (pin "2") (pinfunction "2_2") (pintype "passive"))
      (node (ref "C9") (pin "2") (pinfunction "2_2") (pintype "passive"))
      (node (ref "GROUND") (pin "2") (pinfunction "2_2") (pintype "passive"))
      (node (ref "IC1") (pin "1") (pinfunction "GND/ADJ_1") (pintype "input"))
      (node (ref "IC2") (pin "1") (pinfunction "ADJ_1") (pintype "input"))
      (node (ref "IC3") (pin "11") (pinfunction "GND_11") (pintype "power_in"))
      (node (ref "IC3") (pin "32") (pinfunction "GND1_32") (pintype "power_in"))
      (node (ref "IC3") (pin "62") (pinfunction "GND2_62") (pintype "power_in"))
      (node (ref "IC3") (pin "81") (pinfunction "GND3_81") (pintype "power_in"))
      (node (ref "IC3") (pin "99") (pinfunction "AGND_99") (pintype "power_in"))
      (node (ref "IC4") (pin "3") (pinfunction "GND_3") (pintype "power_in"))
      (node (ref "IC4") (pin "EXP") (pinfunction "PAD_EXP") (pintype "power_in"))
      (node (ref "IC5") (pin "2") (pinfunction "-IN_2") (pintype "input"))
      (node (ref "IC5") (pin "3") (pinfunction "+IN_3") (pintype "input"))
      (node (ref "IC5") (pin "4") (pinfunction "V-_4") (pintype "power_in"))
      (node (ref "IC6") (pin "2") (pinfunction "GND_2") (pintype "power_in"))
      (node (ref "ICSP") (pin "6") (pinfunction "6_6") (pintype "passive"))
      (node (ref "ICSP1") (pin "6") (pinfunction "6_6") (pintype "passive"))
      (node (ref "JP3") (pin "1") (pinfunction "1_1") (pintype "passive"))
      (node (ref "JP4") (pin "1") (pinfunction "1_1") (pintype "passive"))
      (node (ref "L") (pin "C") (pinfunction "C_C") (pintype "passive"))
      (node (ref "ON") (pin "C") (pinfunction "C_C") (pintype "passive"))
      (node (ref "PC1") (pin "-") (pinfunction "-_-") (pintype "passive"))
      (node (ref "PC2") (pin "-") (pinfunction "-_-") (pintype "passive"))
      (node (ref "POWER") (pin "4") (pinfunction "4_4") (pintype "passive"))
      (node (ref "POWER") (pin "5") (pinfunction "5_5") (pintype "passive"))
      (node (ref "PWMH") (pin "7") (pinfunction "7_7") (pintype "passive"))
      (node (ref "RESET") (pin "1") (pinfunction "1_1") (pintype "passive"))
      (node (ref "RESET") (pin "2") (pinfunction "2_2") (pintype "passive"))
      (node (ref "RN5") (pin "2") (pinfunction "1_2") (pintype "passive"))
      (node (ref "UBOOT") (pin "2") (pinfunction "2_2") (pintype "passive"))
      (node (ref "X1") (pin "1") (pinfunction "1_1") (pintype "power_in"))
      (node (ref "X1") (pin "3") (pinfunction "3_3") (pintype "power_in"))
      (node (ref "Y1") (pin "2") (pinfunction "2_2") (pintype "passive"))
      (node (ref "Y2") (pin "2") (pinfunction "2_2") (pintype "passive"))
    )
    (net (code "105") (name "Net-(RN3C-2)") (class "Default")
      (node (ref "ON") (pin "A") (pinfunction "A_A") (pintype "passive"))
      (node (ref "RN3") (pin "6") (pinfunction "2_6") (pintype "passive"))
    )
    (net (code "106") (name "Net-(RN3D-1)") (class "Default")
      (node (ref "L") (pin "A") (pinfunction "A_A") (pintype "passive"))
      (node (ref "RN3") (pin "4") (pinfunction "1_4") (pintype "passive"))
    )
    (net (code "107") (name "Net-(RN4C-1)") (class "Default")
      (node (ref "RN4") (pin "3") (pinfunction "1_3") (pintype "passive"))
      (node (ref "TX") (pin "A") (pinfunction "A_A") (pintype "passive"))
    )
    (net (code "108") (name "Net-(RN4D-1)") (class "Default")
      (node (ref "RN4") (pin "4") (pinfunction "1_4") (pintype "passive"))
      (node (ref "RX") (pin "A") (pinfunction "A_A") (pintype "passive"))
    )
    (net (code "109") (name "unconnected-(IC3-(CLKO{slash}ICP3{slash}INT7)PE7-Pad9)") (class "Default")
      (node (ref "IC3") (pin "9") (pinfunction "(CLKO/ICP3/INT7)PE7_9") (pintype "bidirectional"))
    )
    (net (code "110") (name "unconnected-(IC3-(ICP1)PD4-Pad47)") (class "Default")
      (node (ref "IC3") (pin "47") (pinfunction "(ICP1)PD4_47") (pintype "bidirectional"))
    )
    (net (code "111") (name "unconnected-(IC3-(T1)PD6-Pad49)") (class "Default")
      (node (ref "IC3") (pin "49") (pinfunction "(T1)PD6_49") (pintype "bidirectional"))
    )
    (net (code "112") (name "unconnected-(IC3-(T3{slash}INT6)PE6-Pad8)") (class "Default")
      (node (ref "IC3") (pin "8") (pinfunction "(T3/INT6)PE6_8") (pintype "bidirectional"))
    )
    (net (code "113") (name "unconnected-(IC3-(TOSC1)PG4-Pad29)") (class "Default")
      (node (ref "IC3") (pin "29") (pinfunction "(TOSC1)PG4_29") (pintype "bidirectional"))
    )
    (net (code "114") (name "unconnected-(IC3-(TOSC2)PG3-Pad28)") (class "Default")
      (node (ref "IC3") (pin "28") (pinfunction "(TOSC2)PG3_28") (pintype "bidirectional"))
    )
    (net (code "115") (name "unconnected-(IC3-(XCK0{slash}AIN0)PE2-Pad4)") (class "Default")
      (node (ref "IC3") (pin "4") (pinfunction "(XCK0/AIN0)PE2_4") (pintype "bidirectional"))
    )
    (net (code "116") (name "unconnected-(IC3-(XCK1)PD5-Pad48)") (class "Default")
      (node (ref "IC3") (pin "48") (pinfunction "(XCK1)PD5_48") (pintype "bidirectional"))
    )
    (net (code "117") (name "unconnected-(IC3-PH2(XCK2)-Pad14)") (class "Default")
      (node (ref "IC3") (pin "14") (pinfunction "PH2(XCK2)_14") (pintype "bidirectional"))
    )
    (net (code "118") (name "unconnected-(IC3-PH7(T4)-Pad27)") (class "Default")
      (node (ref "IC3") (pin "27") (pinfunction "PH7(T4)_27") (pintype "bidirectional"))
    )
    (net (code "119") (name "unconnected-(IC3-PJ2(XCK3{slash}PCINT11)-Pad65)") (class "Default")
      (node (ref "IC3") (pin "65") (pinfunction "PJ2(XCK3/PCINT11)_65") (pintype "bidirectional"))
    )
    (net (code "120") (name "unconnected-(IC3-PJ3(PCINT12)-Pad66)") (class "Default")
      (node (ref "IC3") (pin "66") (pinfunction "PJ3(PCINT12)_66") (pintype "bidirectional"))
    )
    (net (code "121") (name "unconnected-(IC3-PJ4(PCINT13)-Pad67)") (class "Default")
      (node (ref "IC3") (pin "67") (pinfunction "PJ4(PCINT13)_67") (pintype "bidirectional"))
    )
    (net (code "122") (name "unconnected-(IC3-PJ5(PCINT14)-Pad68)") (class "Default")
      (node (ref "IC3") (pin "68") (pinfunction "PJ5(PCINT14)_68") (pintype "bidirectional"))
    )
    (net (code "123") (name "unconnected-(IC3-PJ6(PCINT15)-Pad69)") (class "Default")
      (node (ref "IC3") (pin "69") (pinfunction "PJ6(PCINT15)_69") (pintype "bidirectional"))
    )
    (net (code "124") (name "unconnected-(IC3-PJ7-Pad79)") (class "Default")
      (node (ref "IC3") (pin "79") (pinfunction "PJ7_79") (pintype "bidirectional"))
    )
    (net (code "125") (name "unconnected-(IC4-(AIN0{slash}INT1)PD1-Pad7)") (class "Default")
      (node (ref "IC4") (pin "7") (pinfunction "(AIN0/INT1)PD1_7") (pintype "bidirectional"))
    )
    (net (code "126") (name "unconnected-(IC4-(AIN2{slash}PCINT11)PC2-Pad5)") (class "Default")
      (node (ref "IC4") (pin "5") (pinfunction "(AIN2/PCINT11)PC2_5") (pintype "bidirectional"))
    )
    (net (code "127") (name "unconnected-(IC4-(INT4{slash}ICP1{slash}CLK0)PC7-Pad22)") (class "Default")
      (node (ref "IC4") (pin "22") (pinfunction "(INT4/ICP1/CLK0)PC7_22") (pintype "bidirectional"))
    )
    (net (code "128") (name "unconnected-(IC4-(OC0B{slash}INT0)PD0-Pad6)") (class "Default")
      (node (ref "IC4") (pin "6") (pinfunction "(OC0B/INT0)PD0_6") (pintype "bidirectional"))
    )
    (net (code "129") (name "unconnected-(IC4-(OC1A{slash}PCINT8)PC6-Pad23)") (class "Default")
      (node (ref "IC4") (pin "23") (pinfunction "(OC1A/PCINT8)PC6_23") (pintype "bidirectional"))
    )
    (net (code "130") (name "unconnected-(IC4-(PCINT5)PB5-Pad19)") (class "Default")
      (node (ref "IC4") (pin "19") (pinfunction "(PCINT5)PB5_19") (pintype "bidirectional"))
    )
    (net (code "131") (name "unconnected-(IC4-(PCINT6)PB6-Pad20)") (class "Default")
      (node (ref "IC4") (pin "20") (pinfunction "(PCINT6)PB6_20") (pintype "bidirectional"))
    )
    (net (code "132") (name "unconnected-(IC4-(PCINT7{slash}OC0A{slash}OC1C)PB7-Pad21)") (class "Default")
      (node (ref "IC4") (pin "21") (pinfunction "(PCINT7/OC0A/OC1C)PB7_21") (pintype "bidirectional"))
    )
    (net (code "133") (name "unconnected-(IC4-(PCINT9{slash}OC1B)PC5-Pad25)") (class "Default")
      (node (ref "IC4") (pin "25") (pinfunction "(PCINT9/OC1B)PC5_25") (pintype "bidirectional"))
    )
    (net (code "134") (name "unconnected-(IC4-(PCINT10)PC4-Pad26)") (class "Default")
      (node (ref "IC4") (pin "26") (pinfunction "(PCINT10)PC4_26") (pintype "bidirectional"))
    )
    (net (code "135") (name "unconnected-(IC4-(RTS{slash}AIN5{slash}INT6)PD6-Pad12)") (class "Default")
      (node (ref "IC4") (pin "12") (pinfunction "(RTS/AIN5/INT6)PD6_12") (pintype "bidirectional"))
    )
    (net (code "136") (name "unconnected-(IC4-(SS{slash}PCINT0)PB0-Pad14)") (class "Default")
      (node (ref "IC4") (pin "14") (pinfunction "(SS/PCINT0)PB0_14") (pintype "bidirectional"))
    )
    (net (code "137") (name "unconnected-(IC4-(T1{slash}PCINT4)PB4-Pad18)") (class "Default")
      (node (ref "IC4") (pin "18") (pinfunction "(T1/PCINT4)PB4_18") (pintype "bidirectional"))
    )
    (net (code "138") (name "unconnected-(IC5A-OUT-Pad1)") (class "Default")
      (node (ref "IC5") (pin "1") (pinfunction "OUT_1") (pintype "output"))
    )
    (net (code "139") (name "unconnected-(IC6-NC{slash}FB-Pad4)") (class "Default")
      (node (ref "IC6") (pin "4") (pinfunction "NC/FB_4") (pintype "passive"))
    )
    (net (code "140") (name "unconnected-(RN1D-1-Pad4)") (class "Default")
      (node (ref "RN1") (pin "4") (pinfunction "1_4") (pintype "passive"))
    )
    (net (code "141") (name "unconnected-(RN1D-2-Pad5)") (class "Default")
      (node (ref "RN1") (pin "5") (pinfunction "2_5") (pintype "passive"))
    )
    (net (code "142") (name "unconnected-(RN2B-1-Pad2)") (class "Default")
      (node (ref "RN2") (pin "2") (pinfunction "1_2") (pintype "passive"))
    )
    (net (code "143") (name "unconnected-(RN2B-2-Pad7)") (class "Default")
      (node (ref "RN2") (pin "7") (pinfunction "2_7") (pintype "passive"))
    )
    (net (code "144") (name "unconnected-(RN2C-1-Pad3)") (class "Default")
      (node (ref "RN2") (pin "3") (pinfunction "1_3") (pintype "passive"))
    )
    (net (code "145") (name "unconnected-(RN2C-2-Pad6)") (class "Default")
      (node (ref "RN2") (pin "6") (pinfunction "2_6") (pintype "passive"))
    )
    (net (code "146") (name "unconnected-(RN3-Pad1)") (class "Default")
      (node (ref "RN3") (pin "1") (pinfunction "1_1") (pintype "passive"))
    )
    (net (code "147") (name "unconnected-(RN3A-2-Pad8)") (class "Default")
      (node (ref "RN3") (pin "8") (pinfunction "2_8") (pintype "passive"))
    )
    (net (code "148") (name "unconnected-(RN3B-1-Pad2)") (class "Default")
      (node (ref "RN3") (pin "2") (pinfunction "1_2") (pintype "passive"))
    )
    (net (code "149") (name "unconnected-(RN3B-2-Pad7)") (class "Default")
      (node (ref "RN3") (pin "7") (pinfunction "2_7") (pintype "passive"))
    )
    (net (code "150") (name "unconnected-(RN5D-1-Pad4)") (class "Default")
      (node (ref "RN5") (pin "4") (pinfunction "1_4") (pintype "passive"))
    )
    (net (code "151") (name "unconnected-(RN5D-2-Pad5)") (class "Default")
      (node (ref "RN5") (pin "5") (pinfunction "2_5") (pintype "passive"))
    )
  )
)
